# SCH.net
KiCad netlist of a schematic drawn in EasyEDA
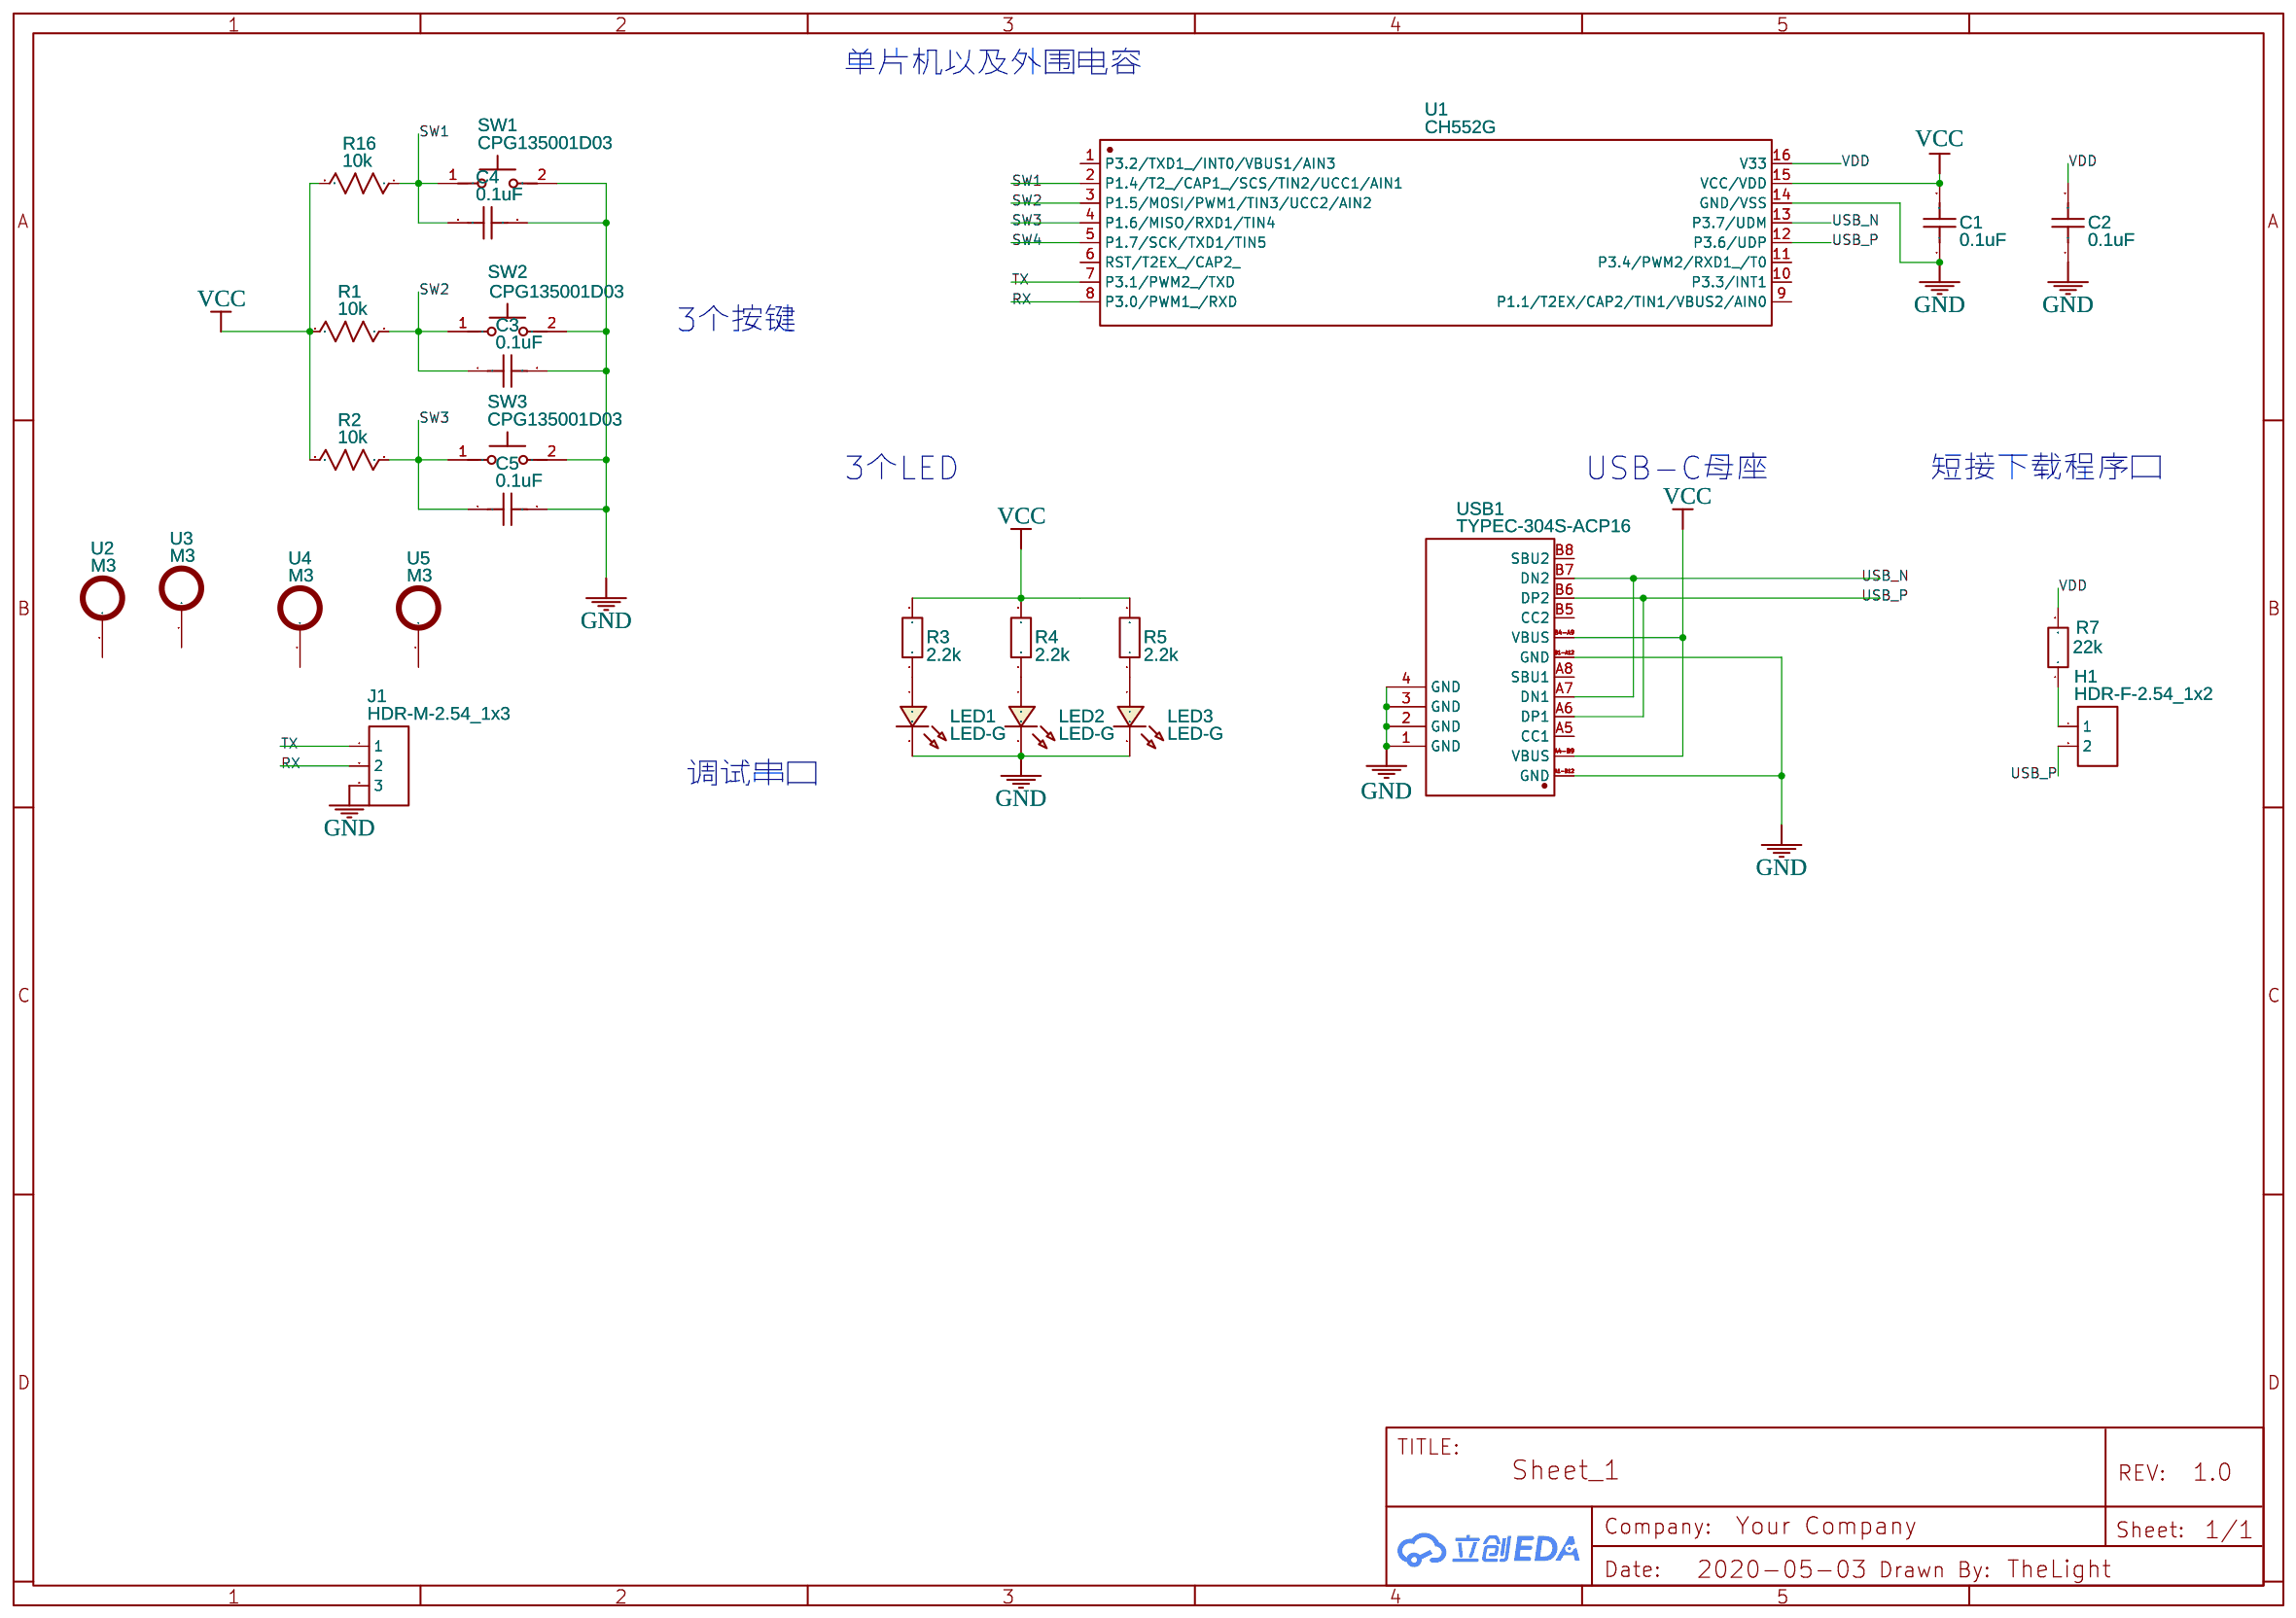
[diagram p0: schematic sheet]

(export (version "E")
  (design (tool "Eeschema 10.0.6"))
  (components
    (comp (ref "C1") (value "0.1uF") (libsource (lib "") (part "C_0201_US")))
    (comp (ref "C2") (value "0.1uF") (libsource (lib "") (part "C_0201_US")))
    (comp (ref "C3")
      (value "0.1uF")
      (fields
        (field (name "BOM_Manufacturer Part") "0603BB104K500NGT")
        (field (name "BOM_Supplier Part") "C2168571")
      )
      (libsource (lib "") (part "0603BB104K500NGT"))
    )
    (comp (ref "C4")
      (value "0.1uF")
      (fields
        (field (name "BOM_Manufacturer Part") "0603BB104K500NGT")
        (field (name "BOM_Supplier Part") "C2168571")
      )
      (libsource (lib "") (part "0603BB104K500NGT"))
    )
    (comp (ref "C5")
      (value "0.1uF")
      (fields
        (field (name "BOM_Manufacturer Part") "0603BB104K500NGT")
        (field (name "BOM_Supplier Part") "C2168571")
      )
      (libsource (lib "") (part "0603BB104K500NGT"))
    )
    (comp (ref "H1")
      (value "HDR-F-2.54_1x2")
      (fields (field (name "BOM_Supplier Part") "C49661"))
      (libsource (lib "") (part "HDR-F-2.54_1x2"))
    )
    (comp (ref "J1")
      (value "HDR-M-2.54_1x3")
      (fields (field (name "BOM_Supplier Part") "C180248"))
      (libsource (lib "") (part "HDR-M-2.54_1x3"))
    )
    (comp (ref "LED1")
      (value "LED-G")
      (fields (field (name "BOM_Manufacturer Part") "NCD0805G1") (field (name "BOM_Supplier Part") "C84260"))
      (libsource (lib "") (part "LED-0805_G"))
    )
    (comp (ref "LED2")
      (value "LED-G")
      (fields (field (name "BOM_Manufacturer Part") "NCD0805G1") (field (name "BOM_Supplier Part") "C84260"))
      (libsource (lib "") (part "LED-0805_G"))
    )
    (comp (ref "LED3")
      (value "LED-G")
      (fields (field (name "BOM_Manufacturer Part") "NCD0805G1") (field (name "BOM_Supplier Part") "C84260"))
      (libsource (lib "") (part "LED-0805_G"))
    )
    (comp (ref "R1") (value "10k") (libsource (lib "") (part "R_0603_US")))
    (comp (ref "R2") (value "10k") (libsource (lib "") (part "R_0603_US")))
    (comp (ref "R3") (value "2.2k") (libsource (lib "") (part "R_0201_EU")))
    (comp (ref "R4") (value "2.2k") (libsource (lib "") (part "R_0201_EU")))
    (comp (ref "R5") (value "2.2k") (libsource (lib "") (part "R_0201_EU")))
    (comp (ref "R7") (value "22k") (libsource (lib "") (part "R_0201_EU")))
    (comp (ref "R16") (value "10k") (libsource (lib "") (part "R_0603_US")))
    (comp (ref "SW1")
      (value "CPG135001D03")
      (fields (field (name "BOM_Supplier Part") "C400231"))
      (libsource (lib "") (part "CPG135001D03"))
    )
    (comp (ref "SW2")
      (value "CPG135001D03")
      (fields (field (name "BOM_Supplier Part") "C400231"))
      (libsource (lib "") (part "CPG135001D03"))
    )
    (comp (ref "SW3")
      (value "CPG135001D03")
      (fields (field (name "BOM_Supplier Part") "C400231"))
      (libsource (lib "") (part "CPG135001D03"))
    )
    (comp (ref "U1")
      (value "CH552G")
      (fields (field (name "BOM_Supplier Part") "C111292"))
      (libsource (lib "") (part "CH552G"))
    )
    (comp (ref "U2") (value "M3") (libsource (lib "") (part "M3")))
    (comp (ref "U3") (value "M3") (libsource (lib "") (part "M3")))
    (comp (ref "U4") (value "M3") (libsource (lib "") (part "M3")))
    (comp (ref "U5") (value "M3") (libsource (lib "") (part "M3")))
    (comp (ref "USB1")
      (value "TYPEC-304S-ACP16")
      (fields (field (name "BOM_Supplier Part") "C720630"))
      (libsource (lib "") (part "TYPEC-304S-ACP16"))
    )
  )
  (nets
    (net (code "1") (name "/RX") (class "Default")
      (node (ref "J1") (pin "2") (pinfunction "2_2") (pintype "input"))
      (node (ref "U1") (pin "8") (pinfunction "P3.0/PWM1_/RXD_8") (pintype "unspecified"))
    )
    (net (code "2") (name "/SW1") (class "Default")
      (node (ref "C4") (pin "1") (pinfunction "1_1") (pintype "unspecified"))
      (node (ref "R16") (pin "1") (pinfunction "1_1") (pintype "unspecified"))
      (node (ref "SW1") (pin "1") (pinfunction "1_1") (pintype "unspecified"))
      (node (ref "U1") (pin "2") (pinfunction "P1.4/T2_/CAP1_/SCS/TIN2/UCC1/AIN1_2") (pintype "unspecified"))
    )
    (net (code "3") (name "/SW2") (class "Default")
      (node (ref "C3") (pin "1") (pinfunction "1_1") (pintype "unspecified"))
      (node (ref "R1") (pin "1") (pinfunction "1_1") (pintype "unspecified"))
      (node (ref "SW2") (pin "1") (pinfunction "1_1") (pintype "unspecified"))
      (node (ref "U1") (pin "3") (pinfunction "P1.5/MOSI/PWM1/TIN3/UCC2/AIN2_3") (pintype "unspecified"))
    )
    (net (code "4") (name "/SW3") (class "Default")
      (node (ref "C5") (pin "1") (pinfunction "1_1") (pintype "unspecified"))
      (node (ref "R2") (pin "1") (pinfunction "1_1") (pintype "unspecified"))
      (node (ref "SW3") (pin "1") (pinfunction "1_1") (pintype "unspecified"))
      (node (ref "U1") (pin "4") (pinfunction "P1.6/MISO/RXD1/TIN4_4") (pintype "unspecified"))
    )
    (net (code "5") (name "/SW4") (class "Default")
      (node (ref "U1") (pin "5") (pinfunction "P1.7/SCK/TXD1/TIN5_5") (pintype "unspecified"))
    )
    (net (code "6") (name "/TX") (class "Default")
      (node (ref "J1") (pin "1") (pinfunction "1_1") (pintype "input"))
      (node (ref "U1") (pin "7") (pinfunction "P3.1/PWM2_/TXD_7") (pintype "unspecified"))
    )
    (net (code "7") (name "/USB_N") (class "Default")
      (node (ref "U1") (pin "13") (pinfunction "P3.7/UDM_13") (pintype "unspecified"))
      (node (ref "USB1") (pin "A7") (pinfunction "DN1_A7") (pintype "unspecified"))
      (node (ref "USB1") (pin "B7") (pinfunction "DN2_B7") (pintype "unspecified"))
    )
    (net (code "8") (name "/USB_P") (class "Default")
      (node (ref "H1") (pin "2") (pinfunction "2_2") (pintype "input"))
      (node (ref "U1") (pin "12") (pinfunction "P3.6/UDP_12") (pintype "unspecified"))
      (node (ref "USB1") (pin "A6") (pinfunction "DP1_A6") (pintype "unspecified"))
      (node (ref "USB1") (pin "B6") (pinfunction "DP2_B6") (pintype "unspecified"))
    )
    (net (code "9") (name "/VDD") (class "Default")
      (node (ref "C2") (pin "2") (pinfunction "2_2") (pintype "unspecified"))
      (node (ref "R7") (pin "2") (pinfunction "2_2") (pintype "unspecified"))
      (node (ref "U1") (pin "16") (pinfunction "V33_16") (pintype "unspecified"))
    )
    (net (code "10") (name "GND") (class "Default")
      (node (ref "C1") (pin "1") (pinfunction "1_1") (pintype "unspecified"))
      (node (ref "C2") (pin "1") (pinfunction "1_1") (pintype "unspecified"))
      (node (ref "C3") (pin "2") (pinfunction "2_2") (pintype "unspecified"))
      (node (ref "C4") (pin "2") (pinfunction "2_2") (pintype "unspecified"))
      (node (ref "C5") (pin "2") (pinfunction "2_2") (pintype "unspecified"))
      (node (ref "J1") (pin "3") (pinfunction "3_3") (pintype "input"))
      (node (ref "LED1") (pin "2") (pinfunction "2_2") (pintype "unspecified"))
      (node (ref "LED2") (pin "2") (pinfunction "2_2") (pintype "unspecified"))
      (node (ref "LED3") (pin "2") (pinfunction "2_2") (pintype "unspecified"))
      (node (ref "SW1") (pin "2") (pinfunction "2_2") (pintype "unspecified"))
      (node (ref "SW2") (pin "2") (pinfunction "2_2") (pintype "unspecified"))
      (node (ref "SW3") (pin "2") (pinfunction "2_2") (pintype "unspecified"))
      (node (ref "U1") (pin "14") (pinfunction "GND/VSS_14") (pintype "unspecified"))
      (node (ref "USB1") (pin "1") (pinfunction "GND_1") (pintype "unspecified"))
      (node (ref "USB1") (pin "2") (pinfunction "GND_2") (pintype "unspecified"))
      (node (ref "USB1") (pin "3") (pinfunction "GND_3") (pintype "unspecified"))
      (node (ref "USB1") (pin "4") (pinfunction "GND_4") (pintype "unspecified"))
      (node (ref "USB1") (pin "A1-B12") (pinfunction "GND_A1-B12") (pintype "unspecified"))
      (node (ref "USB1") (pin "B1-A12") (pinfunction "GND_B1-A12") (pintype "unspecified"))
    )
    (net (code "11") (name "Net-(H1-Pad1)") (class "Default")
      (node (ref "H1") (pin "1") (pinfunction "1_1") (pintype "input"))
      (node (ref "R7") (pin "1") (pinfunction "1_1") (pintype "unspecified"))
    )
    (net (code "12") (name "Net-(LED1-Pad1)") (class "Default")
      (node (ref "LED1") (pin "1") (pinfunction "1_1") (pintype "unspecified"))
      (node (ref "R3") (pin "1") (pinfunction "1_1") (pintype "unspecified"))
    )
    (net (code "13") (name "Net-(LED2-Pad1)") (class "Default")
      (node (ref "LED2") (pin "1") (pinfunction "1_1") (pintype "unspecified"))
      (node (ref "R4") (pin "1") (pinfunction "1_1") (pintype "unspecified"))
    )
    (net (code "14") (name "Net-(LED3-Pad1)") (class "Default")
      (node (ref "LED3") (pin "1") (pinfunction "1_1") (pintype "unspecified"))
      (node (ref "R5") (pin "1") (pinfunction "1_1") (pintype "unspecified"))
    )
    (net (code "15") (name "VCC") (class "Default")
      (node (ref "C1") (pin "2") (pinfunction "2_2") (pintype "unspecified"))
      (node (ref "R1") (pin "2") (pinfunction "2_2") (pintype "unspecified"))
      (node (ref "R16") (pin "2") (pinfunction "2_2") (pintype "unspecified"))
      (node (ref "R2") (pin "2") (pinfunction "2_2") (pintype "unspecified"))
      (node (ref "R3") (pin "2") (pinfunction "2_2") (pintype "unspecified"))
      (node (ref "R4") (pin "2") (pinfunction "2_2") (pintype "unspecified"))
      (node (ref "R5") (pin "2") (pinfunction "2_2") (pintype "unspecified"))
      (node (ref "U1") (pin "15") (pinfunction "VCC/VDD_15") (pintype "unspecified"))
      (node (ref "USB1") (pin "A4-B9") (pinfunction "VBUS_A4-B9") (pintype "unspecified"))
      (node (ref "USB1") (pin "B4-A9") (pinfunction "VBUS_B4-A9") (pintype "unspecified"))
    )
    (net (code "16") (name "unconnected-(U1-P1.1{slash}T2EX{slash}CAP2{slash}TIN1{slash}VBUS2{slash}AIN0-Pad9)") (class "Default")
      (node (ref "U1") (pin "9") (pinfunction "P1.1/T2EX/CAP2/TIN1/VBUS2/AIN0_9") (pintype "unspecified"))
    )
    (net (code "17") (name "unconnected-(U1-P3.2{slash}TXD1_{slash}INT0{slash}VBUS1{slash}AIN3-Pad1)") (class "Default")
      (node (ref "U1") (pin "1") (pinfunction "P3.2/TXD1_/INT0/VBUS1/AIN3_1") (pintype "unspecified"))
    )
    (net (code "18") (name "unconnected-(U1-P3.3{slash}INT1-Pad10)") (class "Default")
      (node (ref "U1") (pin "10") (pinfunction "P3.3/INT1_10") (pintype "unspecified"))
    )
    (net (code "19") (name "unconnected-(U1-P3.4{slash}PWM2{slash}RXD1_{slash}T0-Pad11)") (class "Default")
      (node (ref "U1") (pin "11") (pinfunction "P3.4/PWM2/RXD1_/T0_11") (pintype "unspecified"))
    )
    (net (code "20") (name "unconnected-(U1-RST{slash}T2EX_{slash}CAP2_-Pad6)") (class "Default")
      (node (ref "U1") (pin "6") (pinfunction "RST/T2EX_/CAP2__6") (pintype "unspecified"))
    )
    (net (code "21") (name "unconnected-(U2-Pad1)") (class "Default")
      (node (ref "U2") (pin "1") (pinfunction "1_1") (pintype "unspecified"))
    )
    (net (code "22") (name "unconnected-(U3-Pad1)") (class "Default")
      (node (ref "U3") (pin "1") (pinfunction "1_1") (pintype "unspecified"))
    )
    (net (code "23") (name "unconnected-(U4-Pad1)") (class "Default")
      (node (ref "U4") (pin "1") (pinfunction "1_1") (pintype "unspecified"))
    )
    (net (code "24") (name "unconnected-(U5-Pad1)") (class "Default")
      (node (ref "U5") (pin "1") (pinfunction "1_1") (pintype "unspecified"))
    )
    (net (code "25") (name "unconnected-(USB1-CC1-PadA5)") (class "Default")
      (node (ref "USB1") (pin "A5") (pinfunction "CC1_A5") (pintype "unspecified"))
    )
    (net (code "26") (name "unconnected-(USB1-CC2-PadB5)") (class "Default")
      (node (ref "USB1") (pin "B5") (pinfunction "CC2_B5") (pintype "unspecified"))
    )
    (net (code "27") (name "unconnected-(USB1-SBU1-PadA8)") (class "Default")
      (node (ref "USB1") (pin "A8") (pinfunction "SBU1_A8") (pintype "unspecified"))
    )
    (net (code "28") (name "unconnected-(USB1-SBU2-PadB8)") (class "Default")
      (node (ref "USB1") (pin "B8") (pinfunction "SBU2_B8") (pintype "unspecified"))
    )
  )
)
